# 411_SCH_FINAL.net
KiCad netlist of a schematic drawn in EAGLE
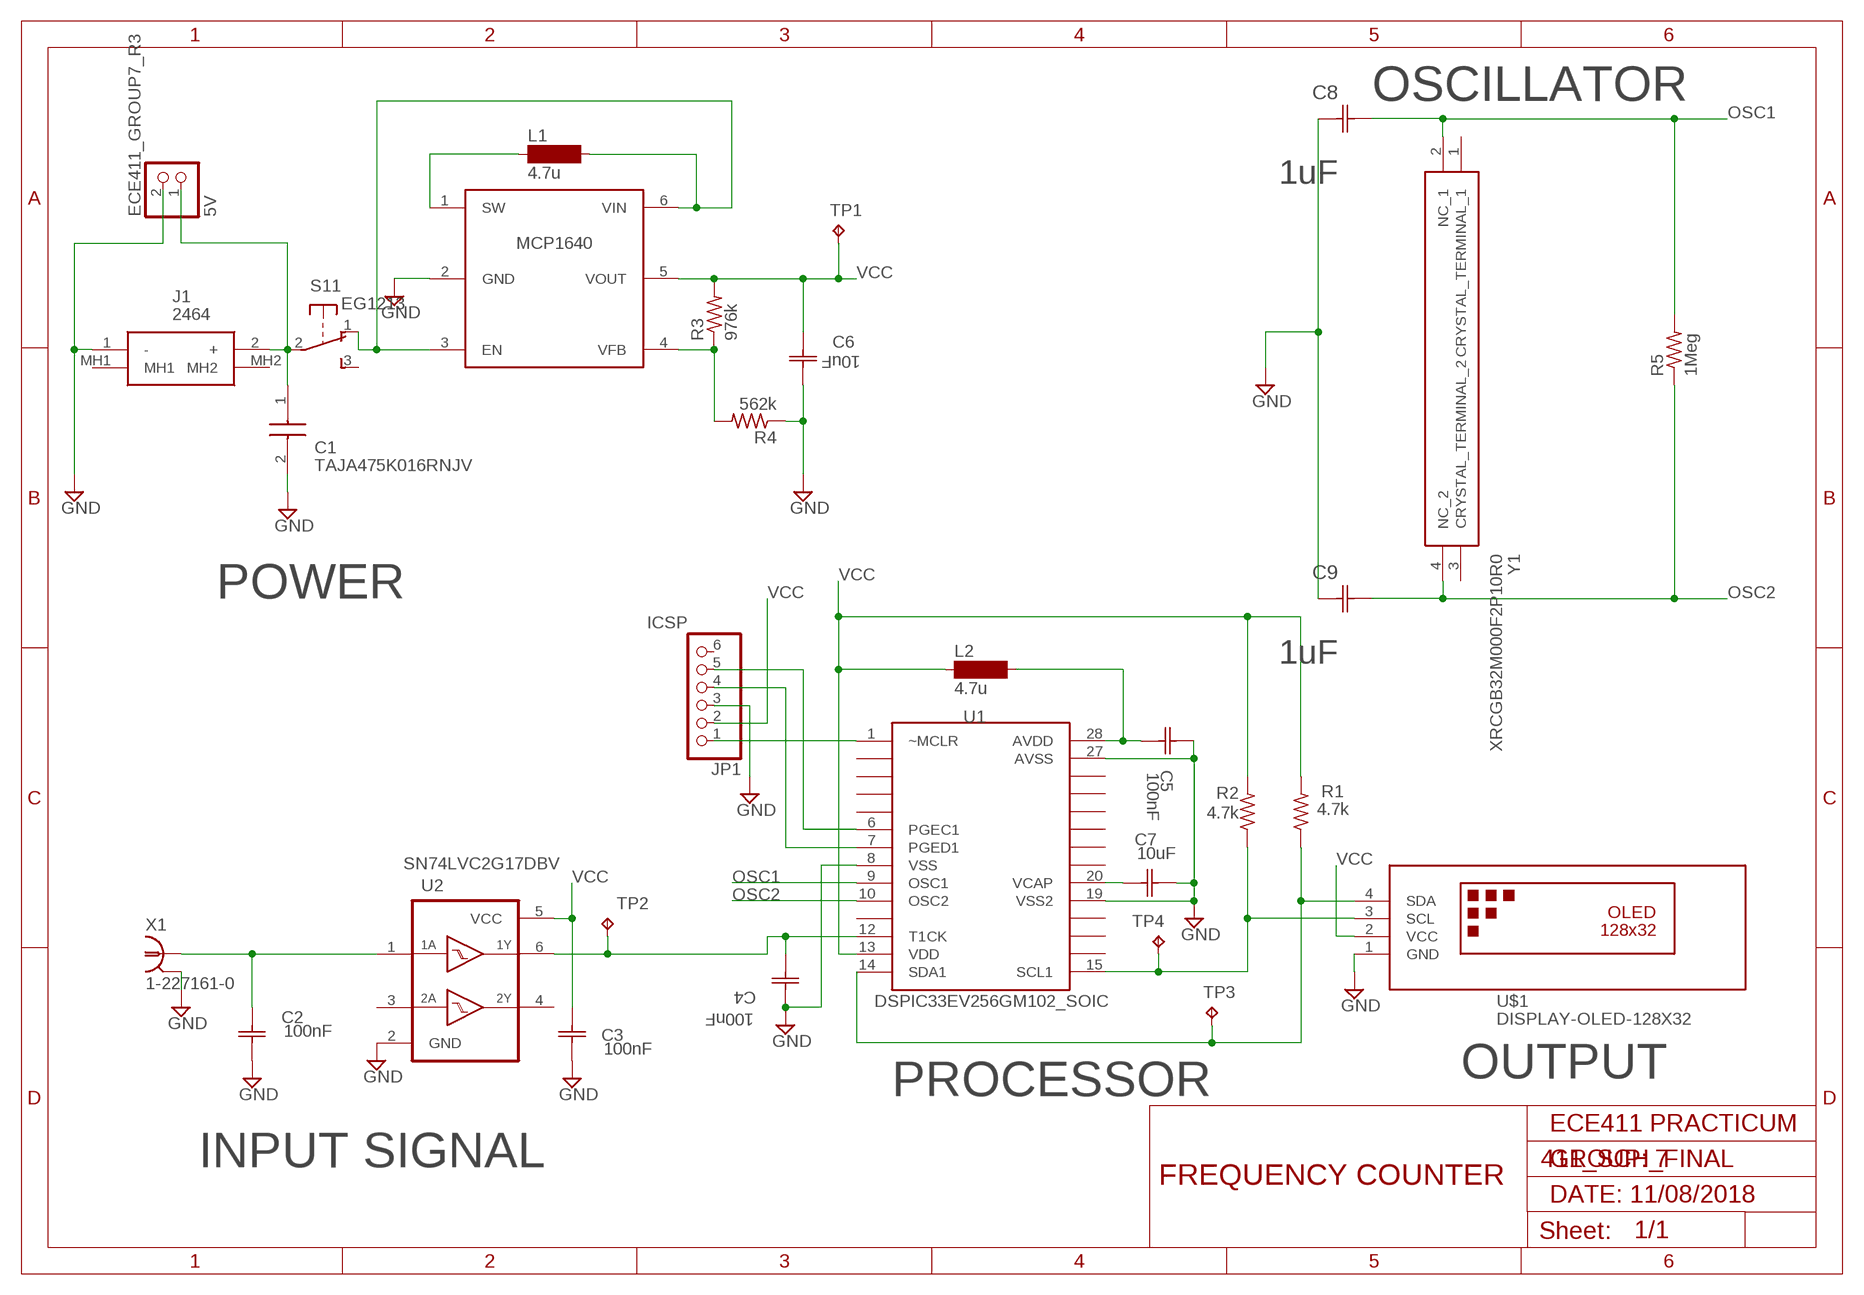
[diagram p0: schematic, sheet 1]

(export (version "E")
  (design (tool "Eeschema 10.0.6"))
  (components
    (comp (ref "C1")
      (value "TAJA475K016RNJV")
      (footprint "eagle-import:CAPPM3216X180N")
      (fields (field (name "MOUSER_PART_NUMBER") "581-TAJA475K016RNJV"))
      (libsource (lib "eagle-import") (part "TAJA475K016RNJV"))
    )
    (comp (ref "C2")
      (value "100nF")
      (footprint "eagle-import:CAPC2013X110N")
      (fields (field (name "MPN") "C0805C104K5RACTU") (field (name "TOLERANCE") "±10%"))
      (libsource (lib "eagle-import") (part "C0805C104K5RACTU"))
    )
    (comp (ref "C3")
      (value "100nF")
      (footprint "eagle-import:CAPC2013X110N")
      (fields (field (name "MPN") "C0805C104K5RACTU") (field (name "TOLERANCE") "±10%"))
      (libsource (lib "eagle-import") (part "C0805C104K5RACTU"))
    )
    (comp (ref "C4")
      (value "100nF")
      (footprint "eagle-import:CAPC2013X110N")
      (fields (field (name "MPN") "C0805C104K5RACTU") (field (name "TOLERANCE") "±10%"))
      (libsource (lib "eagle-import") (part "C0805C104K5RACTU"))
    )
    (comp (ref "C5")
      (value "100nF")
      (footprint "eagle-import:CAPC2013X110N")
      (fields (field (name "MPN") "C0805C104K5RACTU") (field (name "TOLERANCE") "±10%"))
      (libsource (lib "eagle-import") (part "C0805C104K5RACTU"))
    )
    (comp (ref "C6")
      (value "10uF")
      (footprint "eagle-import:CAPC2013X140N")
      (fields (field (name "MPN") "C0805C106K4PACTU") (field (name "TOLERANCE") "±10%"))
      (libsource (lib "eagle-import") (part "C0805C106K4PACTU"))
    )
    (comp (ref "C7")
      (value "10uF")
      (footprint "eagle-import:CAPC2013X140N")
      (fields (field (name "MPN") "C0805C106K4PACTU") (field (name "TOLERANCE") "±10%"))
      (libsource (lib "eagle-import") (part "C0805C106K4PACTU"))
    )
    (comp (ref "C8")
      (value "1uF")
      (footprint "eagle-import:CAPC2013X110N")
      (fields (field (name "MPN") "C0805C105K4RACTU") (field (name "TOLERANCE") "±10%"))
      (libsource (lib "eagle-import") (part "C0805C105K4RACTU"))
    )
    (comp (ref "C9")
      (value "1uF")
      (footprint "eagle-import:CAPC2013X110N")
      (fields (field (name "MPN") "C0805C105K4RACTU") (field (name "TOLERANCE") "±10%"))
      (libsource (lib "eagle-import") (part "C0805C105K4RACTU"))
    )
    (comp (ref "ECE411_GROUP7_R3")
      (value "5V")
      (footprint "eagle-import:JST-PH-2-THM-RA")
      (fields (field (name "MFG") "Harwin Inc.") (field (name "MPN") "M20-9990246"))
      (libsource (lib "eagle-import") (part "JST_2PIN-THM-RA"))
    )
    (comp (ref "J1")
      (value "2464")
      (footprint "eagle-import:2464")
      (fields (field (name "MOUSER_PART_NUMBER") "534-2464"))
      (libsource (lib "eagle-import") (part "2464"))
    )
    (comp (ref "JP1")
      (value "ICSP")
      (footprint "eagle-import:1X06")
      (libsource (lib "eagle-import") (part "PINHD-1X6"))
    )
    (comp (ref "L1")
      (value "4.7u")
      (footprint "eagle-import:SM-1206")
      (libsource (lib "eagle-import") (part "SM-1206"))
    )
    (comp (ref "L2")
      (value "4.7u")
      (footprint "eagle-import:SM-1206")
      (libsource (lib "eagle-import") (part "SM-1206"))
    )
    (comp (ref "MCP1")
      (value "MCP1640")
      (footprint "eagle-import:SOP95P270X145-6")
      (fields (field (name "MFG") "Microchip Technology") (field (name "MPN") "MCP1640DT-I/CHY"))
      (libsource (lib "eagle-import") (part "MCP1640"))
    )
    (comp (ref "R1")
      (value "4.7k")
      (footprint "eagle-import:M2012")
      (fields (field (name "MFG") "Bourns") (field (name "MPN") "CR1206-JW-114ELF"))
      (libsource (lib "eagle-import") (part "R-US_M2012"))
    )
    (comp (ref "R2")
      (value "4.7k")
      (footprint "eagle-import:M2012")
      (fields (field (name "MFG") "Bourns") (field (name "MPN") "CR1206-JW-114ELF"))
      (libsource (lib "eagle-import") (part "R-US_M2012"))
    )
    (comp (ref "R3")
      (value "976k")
      (footprint "eagle-import:R0805")
      (libsource (lib "eagle-import") (part "R-US_R0805"))
    )
    (comp (ref "R4")
      (value "562k")
      (footprint "eagle-import:R0805")
      (libsource (lib "eagle-import") (part "R-US_R0805"))
    )
    (comp (ref "R5")
      (value "1Meg")
      (footprint "eagle-import:M0805")
      (libsource (lib "eagle-import") (part "R-US_M0805"))
    )
    (comp (ref "S1")
      (value "EG1213")
      (footprint "eagle-import:EG1213")
      (libsource (lib "eagle-import") (part "EG1213"))
    )
    (comp (ref "TP1")
      (value "TPB1,27")
      (footprint "eagle-import:B1,27")
      (libsource (lib "eagle-import") (part "TPB1,27"))
    )
    (comp (ref "TP2")
      (value "TPB1,27")
      (footprint "eagle-import:B1,27")
      (libsource (lib "eagle-import") (part "TPB1,27"))
    )
    (comp (ref "TP3")
      (value "TPB1,27")
      (footprint "eagle-import:B1,27")
      (libsource (lib "eagle-import") (part "TPB1,27"))
    )
    (comp (ref "TP4")
      (value "TPB1,27")
      (footprint "eagle-import:B1,27")
      (libsource (lib "eagle-import") (part "TPB1,27"))
    )
    (comp (ref "U$1")
      (value "DISPLAY-OLED-128X32")
      (footprint "eagle-import:DISPLAY-OLED-128X32")
      (fields (field (name "MFG") "Generic") (field (name "MPN") "SSD1306"))
      (libsource (lib "eagle-import") (part "DISPLAY-OLED-128X32"))
    )
    (comp (ref "U1")
      (value "DSPIC33EV256GM102_SOIC")
      (footprint "eagle-import:SOIC127P1020X265-28")
      (fields (field (name "MFG") "Microchip Technology") (field (name "MPN") "DSPIC33EV256GM102"))
      (libsource (lib "eagle-import") (part "DSPIC33EV256GM102_SOIC"))
    )
    (comp (ref "U2")
      (value "SN74LVC2G17DBV")
      (footprint "eagle-import:SOT23-6")
      (fields
        (field (name "MF") "Texas Instruments")
        (field (name "MP") "SN74LVC2G17")
        (field (name "MFG") "ON semiconductor")
      )
      (libsource (lib "eagle-import") (part "SN74LVC2G17DBV"))
    )
    (comp (ref "X1")
      (value "1-227161-0")
      (footprint "eagle-import:AMP_227161")
      (fields (field (name "MF") "TYCO ELECTRONICS") (field (name "MPN") "1-227161"))
      (libsource (lib "eagle-import") (part "?2271611--0"))
    )
    (comp (ref "Y1")
      (value "XRCGB32M000F2P10R0")
      (footprint "eagle-import:XRCGB32_F")
      (fields (field (name "MOUSER_PART_NUMBER") "81-XRCGB32M000F2P1R0"))
      (libsource (lib "eagle-import") (part "XRCGB32M000F2P10R0"))
    )
  )
  (nets
    (net (code "1") (name "/OSC1") (class "Default")
      (node (ref "C8") (pin "2") (pinfunction "C2_2") (pintype "passive"))
      (node (ref "R5") (pin "2") (pinfunction "2_2") (pintype "passive"))
      (node (ref "U1") (pin "9") (pinfunction "OSC1_9") (pintype "bidirectional"))
      (node (ref "Y1") (pin "2") (pinfunction "NC_1_2") (pintype "bidirectional"))
    )
    (net (code "2") (name "/OSC2") (class "Default")
      (node (ref "C9") (pin "2") (pinfunction "C2_2") (pintype "passive"))
      (node (ref "R5") (pin "1") (pinfunction "1_1") (pintype "passive"))
      (node (ref "U1") (pin "10") (pinfunction "OSC2_10") (pintype "bidirectional"))
      (node (ref "Y1") (pin "4") (pinfunction "NC_2_4") (pintype "bidirectional"))
    )
    (net (code "3") (name "/VCC") (class "Default")
      (node (ref "C3") (pin "1") (pinfunction "C1_1") (pintype "passive"))
      (node (ref "C6") (pin "1") (pinfunction "C1_1") (pintype "passive"))
      (node (ref "JP1") (pin "2") (pinfunction "2_2") (pintype "passive"))
      (node (ref "L2") (pin "1") (pinfunction "1_1") (pintype "passive"))
      (node (ref "MCP1") (pin "5") (pinfunction "VOUT_5") (pintype "bidirectional"))
      (node (ref "R1") (pin "2") (pinfunction "2_2") (pintype "passive"))
      (node (ref "R2") (pin "2") (pinfunction "2_2") (pintype "passive"))
      (node (ref "R3") (pin "2") (pinfunction "2_2") (pintype "passive"))
      (node (ref "TP1") (pin "TP") (pinfunction "TP_TP") (pintype "input"))
      (node (ref "U$1") (pin "2") (pinfunction "VCC_2") (pintype "power_in"))
      (node (ref "U1") (pin "13") (pinfunction "VDD_13") (pintype "bidirectional"))
      (node (ref "U2") (pin "5") (pinfunction "VCC_5") (pintype "power_in"))
    )
    (net (code "4") (name "GND") (class "Default")
      (node (ref "C1") (pin "2") (pinfunction "-_2") (pintype "bidirectional"))
      (node (ref "C2") (pin "2") (pinfunction "C2_2") (pintype "passive"))
      (node (ref "C3") (pin "2") (pinfunction "C2_2") (pintype "passive"))
      (node (ref "C4") (pin "2") (pinfunction "C2_2") (pintype "passive"))
      (node (ref "C5") (pin "1") (pinfunction "C1_1") (pintype "passive"))
      (node (ref "C6") (pin "2") (pinfunction "C2_2") (pintype "passive"))
      (node (ref "C7") (pin "2") (pinfunction "C2_2") (pintype "passive"))
      (node (ref "C8") (pin "1") (pinfunction "C1_1") (pintype "passive"))
      (node (ref "C9") (pin "1") (pinfunction "C1_1") (pintype "passive"))
      (node (ref "ECE411_GROUP7_R3") (pin "2") (pinfunction "1_2") (pintype "passive"))
      (node (ref "J1") (pin "1") (pinfunction "-_1") (pintype "bidirectional"))
      (node (ref "JP1") (pin "3") (pinfunction "3_3") (pintype "passive"))
      (node (ref "MCP1") (pin "2") (pinfunction "GND_2") (pintype "bidirectional"))
      (node (ref "R4") (pin "1") (pinfunction "1_1") (pintype "passive"))
      (node (ref "U$1") (pin "1") (pinfunction "GND_1") (pintype "power_in"))
      (node (ref "U1") (pin "19") (pinfunction "VSS2_19") (pintype "bidirectional"))
      (node (ref "U1") (pin "27") (pinfunction "AVSS_27") (pintype "bidirectional"))
      (node (ref "U1") (pin "8") (pinfunction "VSS_8") (pintype "bidirectional"))
      (node (ref "U2") (pin "2") (pinfunction "GND_2") (pintype "power_in"))
      (node (ref "X1") (pin "2") (pinfunction "2_2") (pintype "passive"))
    )
    (net (code "5") (name "Net-(C1-+)") (class "Default")
      (node (ref "C1") (pin "1") (pinfunction "+_1") (pintype "bidirectional"))
      (node (ref "ECE411_GROUP7_R3") (pin "1") (pinfunction "2_1") (pintype "passive"))
      (node (ref "J1") (pin "2") (pinfunction "+_2") (pintype "bidirectional"))
      (node (ref "S1") (pin "2") (pinfunction "P_2") (pintype "passive"))
    )
    (net (code "6") (name "Net-(C2-C1)") (class "Default")
      (node (ref "C2") (pin "1") (pinfunction "C1_1") (pintype "passive"))
      (node (ref "U2") (pin "1") (pinfunction "1A_1") (pintype "input"))
      (node (ref "X1") (pin "1") (pinfunction "1_1") (pintype "passive"))
    )
    (net (code "7") (name "Net-(C4-C1)") (class "Default")
      (node (ref "C4") (pin "1") (pinfunction "C1_1") (pintype "passive"))
      (node (ref "TP2") (pin "TP") (pinfunction "TP_TP") (pintype "input"))
      (node (ref "U1") (pin "12") (pinfunction "T1CK_12") (pintype "bidirectional"))
      (node (ref "U2") (pin "6") (pinfunction "1Y_6") (pintype "output"))
    )
    (net (code "8") (name "Net-(C5-C2)") (class "Default")
      (node (ref "C5") (pin "2") (pinfunction "C2_2") (pintype "passive"))
      (node (ref "L2") (pin "2") (pinfunction "2_2") (pintype "passive"))
      (node (ref "U1") (pin "28") (pinfunction "AVDD_28") (pintype "bidirectional"))
    )
    (net (code "9") (name "Net-(C7-C1)") (class "Default")
      (node (ref "C7") (pin "1") (pinfunction "C1_1") (pintype "passive"))
      (node (ref "U1") (pin "20") (pinfunction "VCAP_20") (pintype "bidirectional"))
    )
    (net (code "10") (name "Net-(MCP1-EN)") (class "Default")
      (node (ref "L1") (pin "2") (pinfunction "2_2") (pintype "passive"))
      (node (ref "MCP1") (pin "3") (pinfunction "EN_3") (pintype "bidirectional"))
      (node (ref "MCP1") (pin "6") (pinfunction "VIN_6") (pintype "bidirectional"))
      (node (ref "S1") (pin "1") (pinfunction "O_1") (pintype "passive"))
    )
    (net (code "11") (name "Net-(MCP1-SW)") (class "Default")
      (node (ref "L1") (pin "1") (pinfunction "1_1") (pintype "passive"))
      (node (ref "MCP1") (pin "1") (pinfunction "SW_1") (pintype "bidirectional"))
    )
    (net (code "12") (name "Net-(MCP1-VFB)") (class "Default")
      (node (ref "MCP1") (pin "4") (pinfunction "VFB_4") (pintype "bidirectional"))
      (node (ref "R3") (pin "1") (pinfunction "1_1") (pintype "passive"))
      (node (ref "R4") (pin "2") (pinfunction "2_2") (pintype "passive"))
    )
    (net (code "13") (name "Net-(U$1-SCL)") (class "Default")
      (node (ref "R2") (pin "1") (pinfunction "1_1") (pintype "passive"))
      (node (ref "TP4") (pin "TP") (pinfunction "TP_TP") (pintype "input"))
      (node (ref "U$1") (pin "3") (pinfunction "SCL_3") (pintype "bidirectional"))
      (node (ref "U1") (pin "15") (pinfunction "SCL1_15") (pintype "bidirectional"))
    )
    (net (code "14") (name "Net-(U$1-SDA)") (class "Default")
      (node (ref "R1") (pin "1") (pinfunction "1_1") (pintype "passive"))
      (node (ref "TP3") (pin "TP") (pinfunction "TP_TP") (pintype "input"))
      (node (ref "U$1") (pin "4") (pinfunction "SDA_4") (pintype "bidirectional"))
      (node (ref "U1") (pin "14") (pinfunction "SDA1_14") (pintype "bidirectional"))
    )
    (net (code "15") (name "Net-(U1-PGEC1)") (class "Default")
      (node (ref "JP1") (pin "5") (pinfunction "5_5") (pintype "passive"))
      (node (ref "U1") (pin "6") (pinfunction "PGEC1_6") (pintype "bidirectional"))
    )
    (net (code "16") (name "Net-(U1-PGED1)") (class "Default")
      (node (ref "JP1") (pin "4") (pinfunction "4_4") (pintype "passive"))
      (node (ref "U1") (pin "7") (pinfunction "PGED1_7") (pintype "bidirectional"))
    )
    (net (code "17") (name "Net-(U1-~{MCLR})") (class "Default")
      (node (ref "JP1") (pin "1") (pinfunction "1_1") (pintype "passive"))
      (node (ref "U1") (pin "1") (pinfunction "~{MCLR}_1") (pintype "bidirectional"))
    )
    (net (code "18") (name "unconnected-(J1-PadMH1)") (class "Default")
      (node (ref "J1") (pin "MH1") (pinfunction "MH1_MH1") (pintype "bidirectional"))
    )
    (net (code "19") (name "unconnected-(J1-PadMH2)") (class "Default")
      (node (ref "J1") (pin "MH2") (pinfunction "MH2_MH2") (pintype "bidirectional"))
    )
    (net (code "20") (name "unconnected-(JP1-Pad6)") (class "Default")
      (node (ref "JP1") (pin "6") (pinfunction "6_6") (pintype "passive"))
    )
    (net (code "21") (name "unconnected-(S1A-S-Pad3)") (class "Default")
      (node (ref "S1") (pin "3") (pinfunction "S_3") (pintype "passive"))
    )
    (net (code "22") (name "unconnected-(U1-P$2-Pad2)") (class "Default")
      (node (ref "U1") (pin "2") (pinfunction "P$2_2") (pintype "bidirectional"))
    )
    (net (code "23") (name "unconnected-(U1-P$3-Pad3)") (class "Default")
      (node (ref "U1") (pin "3") (pinfunction "P$3_3") (pintype "bidirectional"))
    )
    (net (code "24") (name "unconnected-(U1-P$4-Pad4)") (class "Default")
      (node (ref "U1") (pin "4") (pinfunction "P$4_4") (pintype "bidirectional"))
    )
    (net (code "25") (name "unconnected-(U1-P$5-Pad5)") (class "Default")
      (node (ref "U1") (pin "5") (pinfunction "P$5_5") (pintype "bidirectional"))
    )
    (net (code "26") (name "unconnected-(U1-P$11-Pad11)") (class "Default")
      (node (ref "U1") (pin "11") (pinfunction "P$11_11") (pintype "bidirectional"))
    )
    (net (code "27") (name "unconnected-(U1-P$16-Pad16)") (class "Default")
      (node (ref "U1") (pin "16") (pinfunction "P$16_16") (pintype "bidirectional"))
    )
    (net (code "28") (name "unconnected-(U1-P$17-Pad17)") (class "Default")
      (node (ref "U1") (pin "17") (pinfunction "P$17_17") (pintype "bidirectional"))
    )
    (net (code "29") (name "unconnected-(U1-P$18-Pad18)") (class "Default")
      (node (ref "U1") (pin "18") (pinfunction "P$18_18") (pintype "bidirectional"))
    )
    (net (code "30") (name "unconnected-(U1-P$21-Pad21)") (class "Default")
      (node (ref "U1") (pin "21") (pinfunction "P$21_21") (pintype "bidirectional"))
    )
    (net (code "31") (name "unconnected-(U1-P$22-Pad22)") (class "Default")
      (node (ref "U1") (pin "22") (pinfunction "P$22_22") (pintype "bidirectional"))
    )
    (net (code "32") (name "unconnected-(U1-P$23-Pad23)") (class "Default")
      (node (ref "U1") (pin "23") (pinfunction "P$23_23") (pintype "bidirectional"))
    )
    (net (code "33") (name "unconnected-(U1-P$24-Pad24)") (class "Default")
      (node (ref "U1") (pin "24") (pinfunction "P$24_24") (pintype "bidirectional"))
    )
    (net (code "34") (name "unconnected-(U1-P$25-Pad25)") (class "Default")
      (node (ref "U1") (pin "25") (pinfunction "P$25_25") (pintype "bidirectional"))
    )
    (net (code "35") (name "unconnected-(U1-P$26-Pad26)") (class "Default")
      (node (ref "U1") (pin "26") (pinfunction "P$26_26") (pintype "bidirectional"))
    )
    (net (code "36") (name "unconnected-(U2-2A-Pad3)") (class "Default")
      (node (ref "U2") (pin "3") (pinfunction "2A_3") (pintype "input"))
    )
    (net (code "37") (name "unconnected-(U2-2Y-Pad4)") (class "Default")
      (node (ref "U2") (pin "4") (pinfunction "2Y_4") (pintype "output"))
    )
    (net (code "38") (name "unconnected-(Y1-CRYSTAL_TERMINAL_1-Pad1)") (class "Default")
      (node (ref "Y1") (pin "1") (pinfunction "CRYSTAL_TERMINAL_1_1") (pintype "bidirectional"))
    )
    (net (code "39") (name "unconnected-(Y1-CRYSTAL_TERMINAL_2-Pad3)") (class "Default")
      (node (ref "Y1") (pin "3") (pinfunction "CRYSTAL_TERMINAL_2_3") (pintype "bidirectional"))
    )
  )
)
